# Transmiter_FM_v0_1.net
KiCad netlist of a schematic drawn in EAGLE
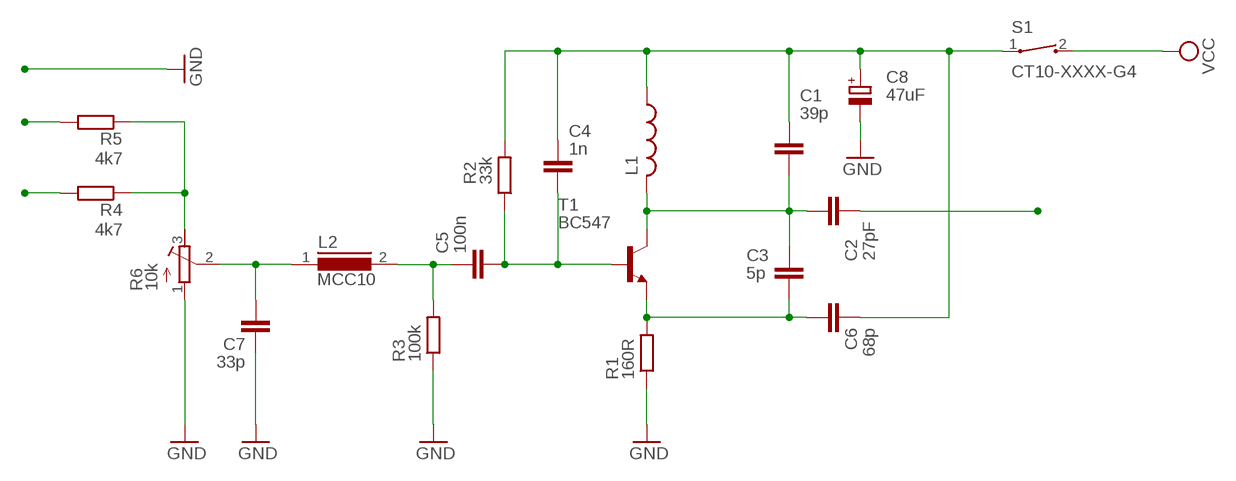
[diagram p0: schematic, sheet 1]

(export (version "E")
  (design (tool "Eeschema 10.0.6"))
  (components
    (comp (ref "C1")
      (value "39p")
      (footprint "eagle-import:C025-024X044")
      (libsource (lib "eagle-import") (part "C-EU025-024X044"))
    )
    (comp (ref "C2")
      (value "27pF")
      (footprint "eagle-import:C025-024X044")
      (libsource (lib "eagle-import") (part "C-EU025-024X044"))
    )
    (comp (ref "C3")
      (value "5p")
      (footprint "eagle-import:C025-024X044")
      (libsource (lib "eagle-import") (part "C-EU025-024X044"))
    )
    (comp (ref "C4")
      (value "1n")
      (footprint "eagle-import:C025-024X044")
      (libsource (lib "eagle-import") (part "C-EU025-024X044"))
    )
    (comp (ref "C5")
      (value "100n")
      (footprint "eagle-import:C025-024X044")
      (libsource (lib "eagle-import") (part "C-EU025-024X044"))
    )
    (comp (ref "C6")
      (value "68p")
      (footprint "eagle-import:C025-024X044")
      (libsource (lib "eagle-import") (part "C-EU025-024X044"))
    )
    (comp (ref "C7")
      (value "33p")
      (footprint "eagle-import:C025-024X044")
      (libsource (lib "eagle-import") (part "C-EU025-024X044"))
    )
    (comp (ref "C8")
      (value "47uF")
      (footprint "eagle-import:E5-10,5")
      (libsource (lib "eagle-import") (part "CPOL-EUE5-10.5"))
    )
    (comp (ref "L1")
      (value "L-US0204/5")
      (footprint "eagle-import:0204_5")
      (libsource (lib "eagle-import") (part "L-US0204/5"))
    )
    (comp (ref "L2")
      (value "MCC10")
      (footprint "eagle-import:MCC10")
      (libsource (lib "eagle-import") (part "MCC10"))
    )
    (comp (ref "R1")
      (value "160R")
      (footprint "eagle-import:0204V")
      (libsource (lib "eagle-import") (part "R-EU_0204/2V"))
    )
    (comp (ref "R2")
      (value "33k")
      (footprint "eagle-import:0204V")
      (libsource (lib "eagle-import") (part "R-EU_0204/2V"))
    )
    (comp (ref "R3")
      (value "100k")
      (footprint "eagle-import:0204V")
      (libsource (lib "eagle-import") (part "R-EU_0204/2V"))
    )
    (comp (ref "R4")
      (value "4k7")
      (footprint "eagle-import:0204V")
      (libsource (lib "eagle-import") (part "R-EU_0204/2V"))
    )
    (comp (ref "R5")
      (value "4k7")
      (footprint "eagle-import:0204V")
      (libsource (lib "eagle-import") (part "R-EU_0204/2V"))
    )
    (comp (ref "R6")
      (value "10k")
      (footprint "eagle-import:RTRIM4G_J")
      (libsource (lib "eagle-import") (part "R-TRIMM4G/J"))
    )
    (comp (ref "S1")
      (value "CT10-XXXX-G4")
      (footprint "eagle-import:CT10-XXXX-G4")
      (libsource (lib "eagle-import") (part "CT10-XXXX-G4"))
    )
    (comp (ref "T1")
      (value "BC547")
      (footprint "eagle-import:TO92")
      (libsource (lib "eagle-import") (part "BC547"))
    )
  )
  (nets
    (net (code "1") (name "GND") (class "Default")
      (node (ref "C7") (pin "1") (pinfunction "1_1") (pintype "passive"))
      (node (ref "C8") (pin "-") (pinfunction "-_-") (pintype "passive"))
      (node (ref "R1") (pin "1") (pinfunction "1_1") (pintype "passive"))
      (node (ref "R3") (pin "1") (pinfunction "1_1") (pintype "passive"))
      (node (ref "R6") (pin "1") (pinfunction "A_1") (pintype "passive"))
    )
    (net (code "2") (name "Net-(C1-Pad1)") (class "Default")
      (node (ref "C1") (pin "1") (pinfunction "1_1") (pintype "passive"))
      (node (ref "C4") (pin "1") (pinfunction "1_1") (pintype "passive"))
      (node (ref "C6") (pin "1") (pinfunction "1_1") (pintype "passive"))
      (node (ref "C8") (pin "+") (pinfunction "+_+") (pintype "passive"))
      (node (ref "L1") (pin "1") (pinfunction "1_1") (pintype "passive"))
      (node (ref "R2") (pin "2") (pinfunction "2_2") (pintype "passive"))
      (node (ref "S1") (pin "1") (pinfunction "1_1") (pintype "passive"))
    )
    (net (code "3") (name "Net-(C5-Pad1)") (class "Default")
      (node (ref "C5") (pin "1") (pinfunction "1_1") (pintype "passive"))
      (node (ref "L2") (pin "2") (pinfunction "2_2") (pintype "passive"))
      (node (ref "R3") (pin "2") (pinfunction "2_2") (pintype "passive"))
    )
    (net (code "4") (name "Net-(R6-E)") (class "Default")
      (node (ref "R4") (pin "1") (pinfunction "1_1") (pintype "passive"))
      (node (ref "R5") (pin "1") (pinfunction "1_1") (pintype "passive"))
      (node (ref "R6") (pin "3") (pinfunction "E_3") (pintype "passive"))
    )
    (net (code "5") (name "Net-(R6-S)") (class "Default")
      (node (ref "C7") (pin "2") (pinfunction "2_2") (pintype "passive"))
      (node (ref "L2") (pin "1") (pinfunction "1_1") (pintype "passive"))
      (node (ref "R6") (pin "2") (pinfunction "S_2") (pintype "passive"))
    )
    (net (code "6") (name "Net-(T1-B)") (class "Default")
      (node (ref "C4") (pin "2") (pinfunction "2_2") (pintype "passive"))
      (node (ref "C5") (pin "2") (pinfunction "2_2") (pintype "passive"))
      (node (ref "R2") (pin "1") (pinfunction "1_1") (pintype "passive"))
      (node (ref "T1") (pin "2") (pinfunction "B_2") (pintype "passive"))
    )
    (net (code "7") (name "Net-(T1-C)") (class "Default")
      (node (ref "C1") (pin "2") (pinfunction "2_2") (pintype "passive"))
      (node (ref "C2") (pin "2") (pinfunction "2_2") (pintype "passive"))
      (node (ref "C3") (pin "1") (pinfunction "1_1") (pintype "passive"))
      (node (ref "L1") (pin "2") (pinfunction "2_2") (pintype "passive"))
      (node (ref "T1") (pin "3") (pinfunction "C_3") (pintype "passive"))
    )
    (net (code "8") (name "Net-(T1-E)") (class "Default")
      (node (ref "C3") (pin "2") (pinfunction "2_2") (pintype "passive"))
      (node (ref "C6") (pin "2") (pinfunction "2_2") (pintype "passive"))
      (node (ref "R1") (pin "2") (pinfunction "2_2") (pintype "passive"))
      (node (ref "T1") (pin "1") (pinfunction "E_1") (pintype "passive"))
    )
    (net (code "9") (name "VCC") (class "Default")
      (node (ref "S1") (pin "2") (pinfunction "2_2") (pintype "passive"))
    )
    (net (code "10") (name "unconnected-(C2-Pad1)") (class "Default")
      (node (ref "C2") (pin "1") (pinfunction "1_1") (pintype "passive"))
    )
    (net (code "11") (name "unconnected-(R4-Pad2)") (class "Default")
      (node (ref "R4") (pin "2") (pinfunction "2_2") (pintype "passive"))
    )
    (net (code "12") (name "unconnected-(R5-Pad2)") (class "Default")
      (node (ref "R5") (pin "2") (pinfunction "2_2") (pintype "passive"))
    )
  )
)
